# LightStickV1_1.net
KiCad netlist of a schematic drawn in EAGLE
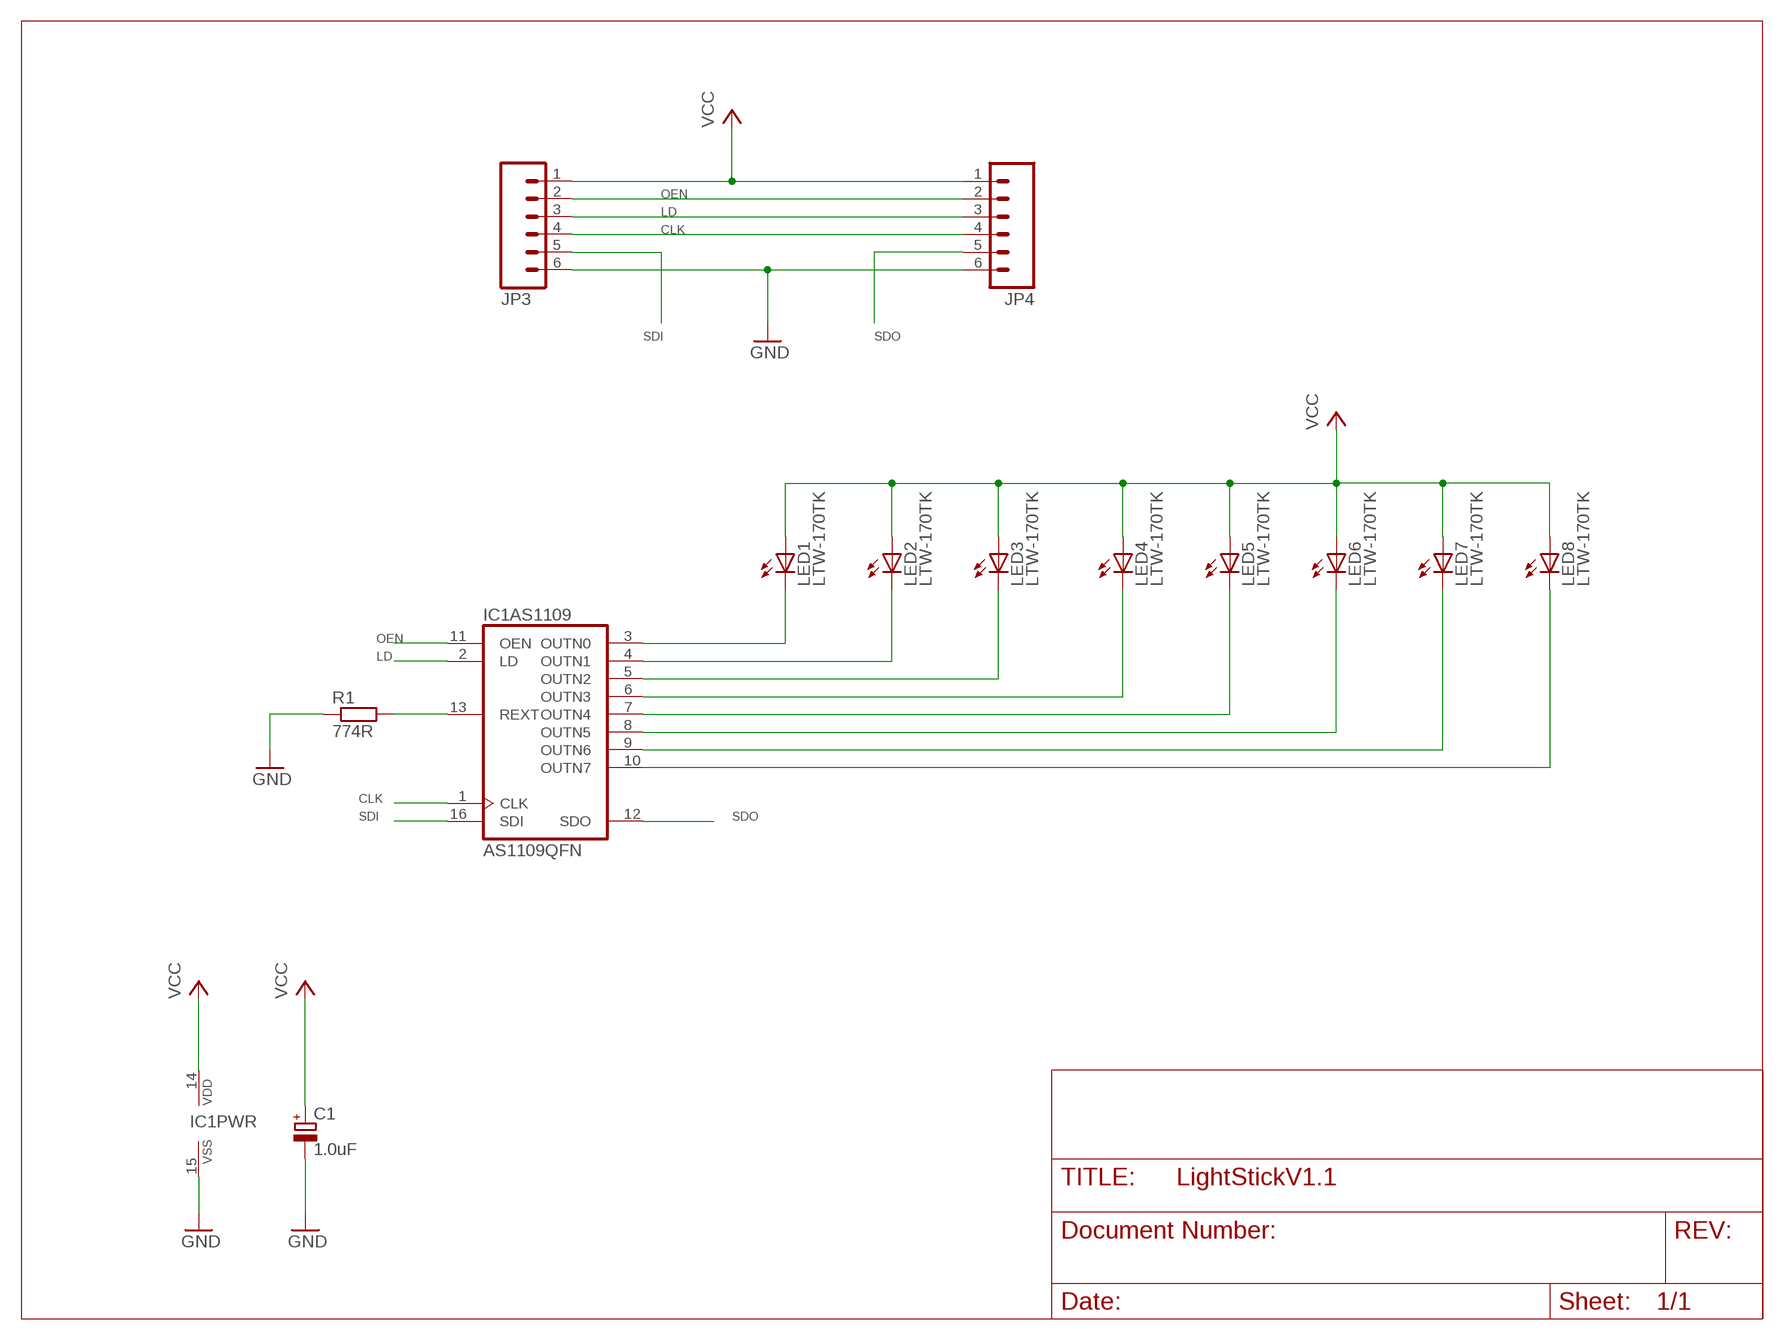
[diagram p0: schematic, sheet 1]

(export (version "E")
  (design (tool "Eeschema 10.0.6"))
  (components
    (comp (ref "C1")
      (value "1.0uF")
      (footprint "eagle-import:SMC_B")
      (libsource (lib "eagle-import") (part "CPOL-EUSMCB"))
    )
    (comp (ref "IC1")
      (value "AS1109QFN")
      (footprint "eagle-import:QFN16-HS")
      (libsource (lib "eagle-import") (part "AS1109QFN"))
    )
    (comp (ref "JP3")
      (value "M06LOCK")
      (footprint "eagle-import:1X06_LOCK")
      (libsource (lib "eagle-import") (part "M06LOCK"))
    )
    (comp (ref "JP4")
      (value "M06LOCK")
      (footprint "eagle-import:1X06_LOCK")
      (libsource (lib "eagle-import") (part "M06LOCK"))
    )
    (comp (ref "LED1")
      (value "LTW-170TK")
      (footprint "eagle-import:CHIPLED_0805")
      (libsource (lib "eagle-import") (part "LEDCHIPLED_0805"))
    )
    (comp (ref "LED2")
      (value "LTW-170TK")
      (footprint "eagle-import:CHIPLED_0805")
      (libsource (lib "eagle-import") (part "LEDCHIPLED_0805"))
    )
    (comp (ref "LED3")
      (value "LTW-170TK")
      (footprint "eagle-import:CHIPLED_0805")
      (libsource (lib "eagle-import") (part "LEDCHIPLED_0805"))
    )
    (comp (ref "LED4")
      (value "LTW-170TK")
      (footprint "eagle-import:CHIPLED_0805")
      (libsource (lib "eagle-import") (part "LEDCHIPLED_0805"))
    )
    (comp (ref "LED5")
      (value "LTW-170TK")
      (footprint "eagle-import:CHIPLED_0805")
      (libsource (lib "eagle-import") (part "LEDCHIPLED_0805"))
    )
    (comp (ref "LED6")
      (value "LTW-170TK")
      (footprint "eagle-import:CHIPLED_0805")
      (libsource (lib "eagle-import") (part "LEDCHIPLED_0805"))
    )
    (comp (ref "LED7")
      (value "LTW-170TK")
      (footprint "eagle-import:CHIPLED_0805")
      (libsource (lib "eagle-import") (part "LEDCHIPLED_0805"))
    )
    (comp (ref "LED8")
      (value "LTW-170TK")
      (footprint "eagle-import:CHIPLED_0805")
      (libsource (lib "eagle-import") (part "LEDCHIPLED_0805"))
    )
    (comp (ref "R1")
      (value "774R")
      (footprint "eagle-import:R0805")
      (libsource (lib "eagle-import") (part "R-EU_R0805"))
    )
  )
  (nets
    (net (code "1") (name "/CLK") (class "Default")
      (node (ref "IC1") (pin "1") (pinfunction "CLK_1") (pintype "input"))
      (node (ref "JP3") (pin "4") (pinfunction "4_4") (pintype "passive"))
      (node (ref "JP4") (pin "4") (pinfunction "4_4") (pintype "passive"))
    )
    (net (code "2") (name "/LD") (class "Default")
      (node (ref "IC1") (pin "2") (pinfunction "LD_2") (pintype "input"))
      (node (ref "JP3") (pin "3") (pinfunction "3_3") (pintype "passive"))
      (node (ref "JP4") (pin "3") (pinfunction "3_3") (pintype "passive"))
    )
    (net (code "3") (name "/OEN") (class "Default")
      (node (ref "IC1") (pin "11") (pinfunction "OEN_11") (pintype "input"))
      (node (ref "JP3") (pin "2") (pinfunction "2_2") (pintype "passive"))
      (node (ref "JP4") (pin "2") (pinfunction "2_2") (pintype "passive"))
    )
    (net (code "4") (name "/SDI") (class "Default")
      (node (ref "IC1") (pin "16") (pinfunction "SDI_16") (pintype "input"))
      (node (ref "JP3") (pin "5") (pinfunction "5_5") (pintype "passive"))
    )
    (net (code "5") (name "/SDO") (class "Default")
      (node (ref "IC1") (pin "12") (pinfunction "SDO_12") (pintype "output"))
      (node (ref "JP4") (pin "5") (pinfunction "5_5") (pintype "passive"))
    )
    (net (code "6") (name "GND") (class "Default")
      (node (ref "C1") (pin "-") (pinfunction "-_-") (pintype "passive"))
      (node (ref "IC1") (pin "15") (pinfunction "VSS_15") (pintype "power_in"))
      (node (ref "JP3") (pin "6") (pinfunction "6_6") (pintype "passive"))
      (node (ref "JP4") (pin "6") (pinfunction "6_6") (pintype "passive"))
      (node (ref "R1") (pin "1") (pinfunction "1_1") (pintype "passive"))
    )
    (net (code "7") (name "Net-(IC1A-OUTN0)") (class "Default")
      (node (ref "IC1") (pin "3") (pinfunction "OUTN0_3") (pintype "output"))
      (node (ref "LED1") (pin "C") (pinfunction "C_C") (pintype "passive"))
    )
    (net (code "8") (name "Net-(IC1A-OUTN1)") (class "Default")
      (node (ref "IC1") (pin "4") (pinfunction "OUTN1_4") (pintype "output"))
      (node (ref "LED2") (pin "C") (pinfunction "C_C") (pintype "passive"))
    )
    (net (code "9") (name "Net-(IC1A-OUTN2)") (class "Default")
      (node (ref "IC1") (pin "5") (pinfunction "OUTN2_5") (pintype "output"))
      (node (ref "LED3") (pin "C") (pinfunction "C_C") (pintype "passive"))
    )
    (net (code "10") (name "Net-(IC1A-OUTN3)") (class "Default")
      (node (ref "IC1") (pin "6") (pinfunction "OUTN3_6") (pintype "output"))
      (node (ref "LED4") (pin "C") (pinfunction "C_C") (pintype "passive"))
    )
    (net (code "11") (name "Net-(IC1A-OUTN4)") (class "Default")
      (node (ref "IC1") (pin "7") (pinfunction "OUTN4_7") (pintype "output"))
      (node (ref "LED5") (pin "C") (pinfunction "C_C") (pintype "passive"))
    )
    (net (code "12") (name "Net-(IC1A-OUTN5)") (class "Default")
      (node (ref "IC1") (pin "8") (pinfunction "OUTN5_8") (pintype "output"))
      (node (ref "LED6") (pin "C") (pinfunction "C_C") (pintype "passive"))
    )
    (net (code "13") (name "Net-(IC1A-OUTN6)") (class "Default")
      (node (ref "IC1") (pin "9") (pinfunction "OUTN6_9") (pintype "output"))
      (node (ref "LED7") (pin "C") (pinfunction "C_C") (pintype "passive"))
    )
    (net (code "14") (name "Net-(IC1A-OUTN7)") (class "Default")
      (node (ref "IC1") (pin "10") (pinfunction "OUTN7_10") (pintype "output"))
      (node (ref "LED8") (pin "C") (pinfunction "C_C") (pintype "passive"))
    )
    (net (code "15") (name "Net-(IC1A-REXT)") (class "Default")
      (node (ref "IC1") (pin "13") (pinfunction "REXT_13") (pintype "input"))
      (node (ref "R1") (pin "2") (pinfunction "2_2") (pintype "passive"))
    )
    (net (code "16") (name "VCC") (class "Default")
      (node (ref "C1") (pin "+") (pinfunction "+_+") (pintype "passive"))
      (node (ref "IC1") (pin "14") (pinfunction "VDD_14") (pintype "power_in"))
      (node (ref "JP3") (pin "1") (pinfunction "1_1") (pintype "passive"))
      (node (ref "JP4") (pin "1") (pinfunction "1_1") (pintype "passive"))
      (node (ref "LED1") (pin "A") (pinfunction "A_A") (pintype "passive"))
      (node (ref "LED2") (pin "A") (pinfunction "A_A") (pintype "passive"))
      (node (ref "LED3") (pin "A") (pinfunction "A_A") (pintype "passive"))
      (node (ref "LED4") (pin "A") (pinfunction "A_A") (pintype "passive"))
      (node (ref "LED5") (pin "A") (pinfunction "A_A") (pintype "passive"))
      (node (ref "LED6") (pin "A") (pinfunction "A_A") (pintype "passive"))
      (node (ref "LED7") (pin "A") (pinfunction "A_A") (pintype "passive"))
      (node (ref "LED8") (pin "A") (pinfunction "A_A") (pintype "passive"))
    )
  )
)
